# DDR.net
KiCad netlist of a schematic drawn in Altium Designer
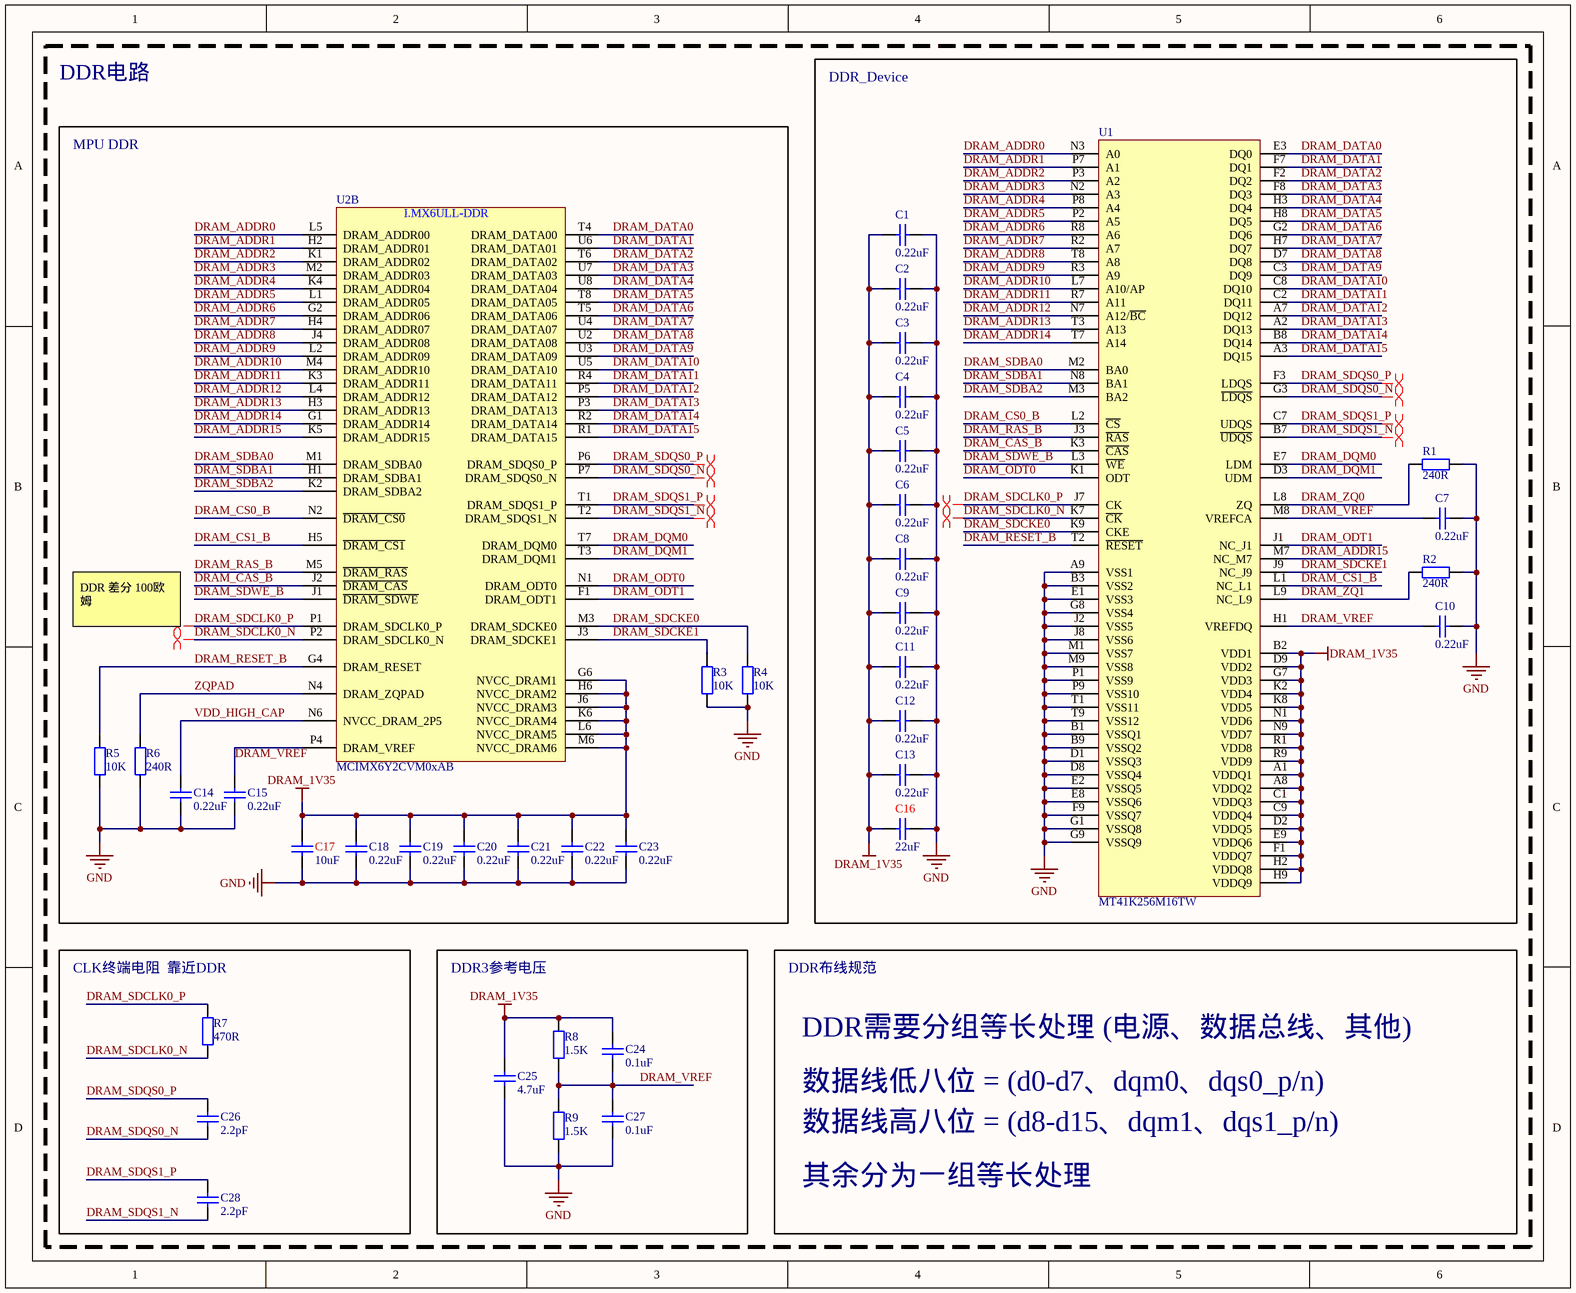
[diagram p0: DDR.SchDoc]

(export (version "E")
  (design (tool "Eeschema 10.0.6"))
  (components
    (comp (ref "C1")
      (value "0.22uF")
      (footprint "0402_C")
      (description "贴片电容")
      (libsource (lib "My_Devices") (part "0402_C"))
    )
    (comp (ref "C2")
      (value "0.22uF")
      (footprint "0402_C")
      (description "贴片电容")
      (libsource (lib "My_Devices") (part "0402_C"))
    )
    (comp (ref "C3")
      (value "0.22uF")
      (footprint "0402_C")
      (description "贴片电容")
      (libsource (lib "My_Devices") (part "0402_C"))
    )
    (comp (ref "C4")
      (value "0.22uF")
      (footprint "0402_C")
      (description "贴片电容")
      (libsource (lib "My_Devices") (part "0402_C"))
    )
    (comp (ref "C5")
      (value "0.22uF")
      (footprint "0402_C")
      (description "贴片电容")
      (libsource (lib "My_Devices") (part "0402_C"))
    )
    (comp (ref "C6")
      (value "0.22uF")
      (footprint "0402_C")
      (description "贴片电容")
      (libsource (lib "My_Devices") (part "0402_C"))
    )
    (comp (ref "C7")
      (value "0.22uF")
      (footprint "0402_C")
      (description "贴片电容")
      (libsource (lib "My_Devices") (part "0402_C"))
    )
    (comp (ref "C8")
      (value "0.22uF")
      (footprint "0402_C")
      (description "贴片电容")
      (libsource (lib "My_Devices") (part "0402_C"))
    )
    (comp (ref "C9")
      (value "0.22uF")
      (footprint "0402_C")
      (description "贴片电容")
      (libsource (lib "My_Devices") (part "0402_C"))
    )
    (comp (ref "C10")
      (value "0.22uF")
      (footprint "0402_C")
      (description "贴片电容")
      (libsource (lib "My_Devices") (part "0402_C"))
    )
    (comp (ref "C11")
      (value "0.22uF")
      (footprint "0402_C")
      (description "贴片电容")
      (libsource (lib "My_Devices") (part "0402_C"))
    )
    (comp (ref "C12")
      (value "0.22uF")
      (footprint "0402_C")
      (description "贴片电容")
      (libsource (lib "My_Devices") (part "0402_C"))
    )
    (comp (ref "C13")
      (value "0.22uF")
      (footprint "0402_C")
      (description "贴片电容")
      (libsource (lib "My_Devices") (part "0402_C"))
    )
    (comp (ref "C14")
      (value "0.22uF")
      (footprint "0402_C")
      (description "贴片电容")
      (libsource (lib "My_Devices") (part "0402_C"))
    )
    (comp (ref "C15")
      (value "0.22uF")
      (footprint "0402_C")
      (description "贴片电容")
      (libsource (lib "My_Devices") (part "0402_C"))
    )
    (comp (ref "C16")
      (value "22uF")
      (footprint "0603_C _MINI")
      (description "贴片电容")
      (libsource (lib "My_Devices") (part "0603_C_MINI"))
    )
    (comp (ref "C17")
      (value "10uF")
      (footprint "0603_C _MINI")
      (description "贴片电容")
      (libsource (lib "My_Devices") (part "0603_C_MINI"))
    )
    (comp (ref "C18")
      (value "0.22uF")
      (footprint "0402_C")
      (description "贴片电容")
      (libsource (lib "My_Devices") (part "0402_C"))
    )
    (comp (ref "C19")
      (value "0.22uF")
      (footprint "0402_C")
      (description "贴片电容")
      (libsource (lib "My_Devices") (part "0402_C"))
    )
    (comp (ref "C20")
      (value "0.22uF")
      (footprint "0402_C")
      (description "贴片电容")
      (libsource (lib "My_Devices") (part "0402_C"))
    )
    (comp (ref "C21")
      (value "0.22uF")
      (footprint "0402_C")
      (description "贴片电容")
      (libsource (lib "My_Devices") (part "0402_C"))
    )
    (comp (ref "C22")
      (value "0.22uF")
      (footprint "0402_C")
      (description "贴片电容")
      (libsource (lib "My_Devices") (part "0402_C"))
    )
    (comp (ref "C23")
      (value "0.22uF")
      (footprint "0402_C")
      (description "贴片电容")
      (libsource (lib "My_Devices") (part "0402_C"))
    )
    (comp (ref "C24")
      (value "0.1uF")
      (footprint "0402_C")
      (description "贴片电容")
      (libsource (lib "My_Devices") (part "0402_C"))
    )
    (comp (ref "C25")
      (value "4.7uF")
      (footprint "0402_C")
      (description "贴片电容")
      (libsource (lib "My_Devices") (part "0402_C"))
    )
    (comp (ref "C26")
      (value "2.2pF")
      (footprint "0402_C")
      (description "贴片电容")
      (libsource (lib "My_Devices") (part "0402_C"))
    )
    (comp (ref "C27")
      (value "0.1uF")
      (footprint "0402_C")
      (description "贴片电容")
      (libsource (lib "My_Devices") (part "0402_C"))
    )
    (comp (ref "C28")
      (value "2.2pF")
      (footprint "0402_C")
      (description "贴片电容")
      (libsource (lib "My_Devices") (part "0402_C"))
    )
    (comp (ref "R1")
      (value "240R")
      (footprint "0402_R")
      (description "贴片电阻")
      (libsource (lib "My_Devices") (part "0402_R"))
    )
    (comp (ref "R2")
      (value "240R")
      (footprint "0402_R")
      (description "贴片电阻")
      (libsource (lib "My_Devices") (part "0402_R"))
    )
    (comp (ref "R3")
      (value "10K")
      (footprint "0402_R")
      (description "贴片电阻")
      (libsource (lib "") (part "0402_R_1"))
    )
    (comp (ref "R4")
      (value "10K")
      (footprint "0402_R")
      (description "贴片电阻")
      (libsource (lib "") (part "0402_R_1"))
    )
    (comp (ref "R5")
      (value "10K")
      (footprint "0402_R")
      (description "贴片电阻")
      (libsource (lib "") (part "0402_R_1"))
    )
    (comp (ref "R6")
      (value "240R")
      (footprint "0402_R")
      (description "贴片电阻")
      (libsource (lib "") (part "0402_R_1"))
    )
    (comp (ref "R7")
      (value "470R")
      (footprint "0402_R")
      (description "贴片电阻")
      (libsource (lib "") (part "0402_R_1"))
    )
    (comp (ref "R8")
      (value "1.5K")
      (footprint "0402_R")
      (description "贴片电阻")
      (libsource (lib "") (part "0402_R_1"))
    )
    (comp (ref "R9")
      (value "1.5K")
      (footprint "0402_R")
      (description "贴片电阻")
      (libsource (lib "") (part "0402_R_1"))
    )
    (comp (ref "U1")
      (value "MT41K256M16TW")
      (footprint "BGA96")
      (libsource (lib "Linux_Core") (part "MT41K256M16TW"))
    )
    (comp (ref "U2")
      (value "MCIMX6Y2CVM0xAB")
      (footprint "BGA289_17x17_0.8Pitch")
      (libsource (lib "Linux_Core") (part "MCIMX6Y2CVM0xAB"))
    )
  )
  (nets
    (net (code "1") (name "/DRAM_ADDR0") (class "Default")
      (node (ref "U1") (pin "N3") (pinfunction "A0_N3") (pintype "passive"))
      (node (ref "U2") (pin "L5") (pinfunction "DRAM_ADDR00_L5") (pintype "passive"))
    )
    (net (code "2") (name "/DRAM_ADDR1") (class "Default")
      (node (ref "U1") (pin "P7") (pinfunction "A1_P7") (pintype "passive"))
      (node (ref "U2") (pin "H2") (pinfunction "DRAM_ADDR01_H2") (pintype "passive"))
    )
    (net (code "3") (name "/DRAM_ADDR2") (class "Default")
      (node (ref "U1") (pin "P3") (pinfunction "A2_P3") (pintype "passive"))
      (node (ref "U2") (pin "K1") (pinfunction "DRAM_ADDR02_K1") (pintype "passive"))
    )
    (net (code "4") (name "/DRAM_ADDR3") (class "Default")
      (node (ref "U1") (pin "N2") (pinfunction "A3_N2") (pintype "passive"))
      (node (ref "U2") (pin "M2") (pinfunction "DRAM_ADDR03_M2") (pintype "passive"))
    )
    (net (code "5") (name "/DRAM_ADDR4") (class "Default")
      (node (ref "U1") (pin "P8") (pinfunction "A4_P8") (pintype "passive"))
      (node (ref "U2") (pin "K4") (pinfunction "DRAM_ADDR04_K4") (pintype "passive"))
    )
    (net (code "6") (name "/DRAM_ADDR5") (class "Default")
      (node (ref "U1") (pin "P2") (pinfunction "A5_P2") (pintype "passive"))
      (node (ref "U2") (pin "L1") (pinfunction "DRAM_ADDR05_L1") (pintype "passive"))
    )
    (net (code "7") (name "/DRAM_ADDR6") (class "Default")
      (node (ref "U1") (pin "R8") (pinfunction "A6_R8") (pintype "passive"))
      (node (ref "U2") (pin "G2") (pinfunction "DRAM_ADDR06_G2") (pintype "passive"))
    )
    (net (code "8") (name "/DRAM_ADDR7") (class "Default")
      (node (ref "U1") (pin "R2") (pinfunction "A7_R2") (pintype "passive"))
      (node (ref "U2") (pin "H4") (pinfunction "DRAM_ADDR07_H4") (pintype "passive"))
    )
    (net (code "9") (name "/DRAM_ADDR8") (class "Default")
      (node (ref "U1") (pin "T8") (pinfunction "A8_T8") (pintype "passive"))
      (node (ref "U2") (pin "J4") (pinfunction "DRAM_ADDR08_J4") (pintype "passive"))
    )
    (net (code "10") (name "/DRAM_ADDR9") (class "Default")
      (node (ref "U1") (pin "R3") (pinfunction "A9_R3") (pintype "passive"))
      (node (ref "U2") (pin "L2") (pinfunction "DRAM_ADDR09_L2") (pintype "passive"))
    )
    (net (code "11") (name "/DRAM_ADDR10") (class "Default")
      (node (ref "U1") (pin "L7") (pinfunction "A10/AP_L7") (pintype "passive"))
      (node (ref "U2") (pin "M4") (pinfunction "DRAM_ADDR10_M4") (pintype "passive"))
    )
    (net (code "12") (name "/DRAM_ADDR11") (class "Default")
      (node (ref "U1") (pin "R7") (pinfunction "A11_R7") (pintype "passive"))
      (node (ref "U2") (pin "K3") (pinfunction "DRAM_ADDR11_K3") (pintype "passive"))
    )
    (net (code "13") (name "/DRAM_ADDR12") (class "Default")
      (node (ref "U1") (pin "N7") (pinfunction "A12/~{BC}_N7") (pintype "passive"))
      (node (ref "U2") (pin "L4") (pinfunction "DRAM_ADDR12_L4") (pintype "passive"))
    )
    (net (code "14") (name "/DRAM_ADDR13") (class "Default")
      (node (ref "U1") (pin "T3") (pinfunction "A13_T3") (pintype "passive"))
      (node (ref "U2") (pin "H3") (pinfunction "DRAM_ADDR13_H3") (pintype "passive"))
    )
    (net (code "15") (name "/DRAM_ADDR14") (class "Default")
      (node (ref "U1") (pin "T7") (pinfunction "A14_T7") (pintype "passive"))
      (node (ref "U2") (pin "G1") (pinfunction "DRAM_ADDR14_G1") (pintype "passive"))
    )
    (net (code "16") (name "/DRAM_ADDR15") (class "Default")
      (node (ref "U1") (pin "M7") (pinfunction "NC_M7_M7") (pintype "passive"))
      (node (ref "U2") (pin "K5") (pinfunction "DRAM_ADDR15_K5") (pintype "passive"))
    )
    (net (code "17") (name "/DRAM_CAS_B") (class "Default")
      (node (ref "U1") (pin "K3") (pinfunction "~{CAS}_K3") (pintype "passive"))
      (node (ref "U2") (pin "J2") (pinfunction "~{DRAM_CAS}_J2") (pintype "passive"))
    )
    (net (code "18") (name "/DRAM_CS0_B") (class "Default")
      (node (ref "U1") (pin "L2") (pinfunction "~{CS}_L2") (pintype "passive"))
      (node (ref "U2") (pin "N2") (pinfunction "~{DRAM_CS0}_N2") (pintype "passive"))
    )
    (net (code "19") (name "/DRAM_CS1_B") (class "Default")
      (node (ref "U1") (pin "L1") (pinfunction "NC_L1_L1") (pintype "passive"))
      (node (ref "U2") (pin "H5") (pinfunction "~{DRAM_CS1}_H5") (pintype "passive"))
    )
    (net (code "20") (name "/DRAM_DATA0") (class "Default")
      (node (ref "U1") (pin "E3") (pinfunction "DQ0_E3") (pintype "passive"))
      (node (ref "U2") (pin "T4") (pinfunction "DRAM_DATA00_T4") (pintype "passive"))
    )
    (net (code "21") (name "/DRAM_DATA1") (class "Default")
      (node (ref "U1") (pin "F7") (pinfunction "DQ1_F7") (pintype "passive"))
      (node (ref "U2") (pin "U6") (pinfunction "DRAM_DATA01_U6") (pintype "passive"))
    )
    (net (code "22") (name "/DRAM_DATA2") (class "Default")
      (node (ref "U1") (pin "F2") (pinfunction "DQ2_F2") (pintype "passive"))
      (node (ref "U2") (pin "T6") (pinfunction "DRAM_DATA02_T6") (pintype "passive"))
    )
    (net (code "23") (name "/DRAM_DATA3") (class "Default")
      (node (ref "U1") (pin "F8") (pinfunction "DQ3_F8") (pintype "passive"))
      (node (ref "U2") (pin "U7") (pinfunction "DRAM_DATA03_U7") (pintype "passive"))
    )
    (net (code "24") (name "/DRAM_DATA4") (class "Default")
      (node (ref "U1") (pin "H3") (pinfunction "DQ4_H3") (pintype "passive"))
      (node (ref "U2") (pin "U8") (pinfunction "DRAM_DATA04_U8") (pintype "passive"))
    )
    (net (code "25") (name "/DRAM_DATA5") (class "Default")
      (node (ref "U1") (pin "H8") (pinfunction "DQ5_H8") (pintype "passive"))
      (node (ref "U2") (pin "T8") (pinfunction "DRAM_DATA05_T8") (pintype "passive"))
    )
    (net (code "26") (name "/DRAM_DATA6") (class "Default")
      (node (ref "U1") (pin "G2") (pinfunction "DQ6_G2") (pintype "passive"))
      (node (ref "U2") (pin "T5") (pinfunction "DRAM_DATA06_T5") (pintype "passive"))
    )
    (net (code "27") (name "/DRAM_DATA7") (class "Default")
      (node (ref "U1") (pin "H7") (pinfunction "DQ7_H7") (pintype "passive"))
      (node (ref "U2") (pin "U4") (pinfunction "DRAM_DATA07_U4") (pintype "passive"))
    )
    (net (code "28") (name "/DRAM_DATA8") (class "Default")
      (node (ref "U1") (pin "D7") (pinfunction "DQ8_D7") (pintype "passive"))
      (node (ref "U2") (pin "U2") (pinfunction "DRAM_DATA08_U2") (pintype "passive"))
    )
    (net (code "29") (name "/DRAM_DATA9") (class "Default")
      (node (ref "U1") (pin "C3") (pinfunction "DQ9_C3") (pintype "passive"))
      (node (ref "U2") (pin "U3") (pinfunction "DRAM_DATA09_U3") (pintype "passive"))
    )
    (net (code "30") (name "/DRAM_DATA10") (class "Default")
      (node (ref "U1") (pin "C8") (pinfunction "DQ10_C8") (pintype "passive"))
      (node (ref "U2") (pin "U5") (pinfunction "DRAM_DATA10_U5") (pintype "passive"))
    )
    (net (code "31") (name "/DRAM_DATA11") (class "Default")
      (node (ref "U1") (pin "C2") (pinfunction "DQ11_C2") (pintype "passive"))
      (node (ref "U2") (pin "R4") (pinfunction "DRAM_DATA11_R4") (pintype "passive"))
    )
    (net (code "32") (name "/DRAM_DATA12") (class "Default")
      (node (ref "U1") (pin "A7") (pinfunction "DQ12_A7") (pintype "passive"))
      (node (ref "U2") (pin "P5") (pinfunction "DRAM_DATA12_P5") (pintype "passive"))
    )
    (net (code "33") (name "/DRAM_DATA13") (class "Default")
      (node (ref "U1") (pin "A2") (pinfunction "DQ13_A2") (pintype "passive"))
      (node (ref "U2") (pin "P3") (pinfunction "DRAM_DATA13_P3") (pintype "passive"))
    )
    (net (code "34") (name "/DRAM_DATA14") (class "Default")
      (node (ref "U1") (pin "B8") (pinfunction "DQ14_B8") (pintype "passive"))
      (node (ref "U2") (pin "R2") (pinfunction "DRAM_DATA14_R2") (pintype "passive"))
    )
    (net (code "35") (name "/DRAM_DATA15") (class "Default")
      (node (ref "U1") (pin "A3") (pinfunction "DQ15_A3") (pintype "passive"))
      (node (ref "U2") (pin "R1") (pinfunction "DRAM_DATA15_R1") (pintype "passive"))
    )
    (net (code "36") (name "/DRAM_DQM0") (class "Default")
      (node (ref "U1") (pin "E7") (pinfunction "LDM_E7") (pintype "passive"))
      (node (ref "U2") (pin "T7") (pinfunction "DRAM_DQM0_T7") (pintype "passive"))
    )
    (net (code "37") (name "/DRAM_DQM1") (class "Default")
      (node (ref "U1") (pin "D3") (pinfunction "UDM_D3") (pintype "passive"))
      (node (ref "U2") (pin "T3") (pinfunction "DRAM_DQM1_T3") (pintype "passive"))
    )
    (net (code "38") (name "/DRAM_ODT0") (class "Default")
      (node (ref "U1") (pin "K1") (pinfunction "ODT_K1") (pintype "passive"))
      (node (ref "U2") (pin "N1") (pinfunction "DRAM_ODT0_N1") (pintype "passive"))
    )
    (net (code "39") (name "/DRAM_ODT1") (class "Default")
      (node (ref "U1") (pin "J1") (pinfunction "NC_J1_J1") (pintype "passive"))
      (node (ref "U2") (pin "F1") (pinfunction "DRAM_ODT1_F1") (pintype "passive"))
    )
    (net (code "40") (name "/DRAM_RAS_B") (class "Default")
      (node (ref "U1") (pin "J3") (pinfunction "~{RAS}_J3") (pintype "passive"))
      (node (ref "U2") (pin "M5") (pinfunction "~{DRAM_RAS}_M5") (pintype "passive"))
    )
    (net (code "41") (name "/DRAM_RESET_B") (class "Default")
      (node (ref "R5") (pin "2") (pinfunction "2_2") (pintype "passive"))
      (node (ref "U1") (pin "T2") (pinfunction "~{RESET}_T2") (pintype "passive"))
      (node (ref "U2") (pin "G4") (pinfunction "DRAM_RESET_G4") (pintype "passive"))
    )
    (net (code "42") (name "/DRAM_SDBA0") (class "Default")
      (node (ref "U1") (pin "M2") (pinfunction "BA0_M2") (pintype "passive"))
      (node (ref "U2") (pin "M1") (pinfunction "DRAM_SDBA0_M1") (pintype "passive"))
    )
    (net (code "43") (name "/DRAM_SDBA1") (class "Default")
      (node (ref "U1") (pin "N8") (pinfunction "BA1_N8") (pintype "passive"))
      (node (ref "U2") (pin "H1") (pinfunction "DRAM_SDBA1_H1") (pintype "passive"))
    )
    (net (code "44") (name "/DRAM_SDBA2") (class "Default")
      (node (ref "U1") (pin "M3") (pinfunction "BA2_M3") (pintype "passive"))
      (node (ref "U2") (pin "K2") (pinfunction "DRAM_SDBA2_K2") (pintype "passive"))
    )
    (net (code "45") (name "/DRAM_SDCKE0") (class "Default")
      (node (ref "R4") (pin "2") (pinfunction "2_2") (pintype "passive"))
      (node (ref "U1") (pin "K9") (pinfunction "CKE_K9") (pintype "passive"))
      (node (ref "U2") (pin "M3") (pinfunction "DRAM_SDCKE0_M3") (pintype "passive"))
    )
    (net (code "46") (name "/DRAM_SDCKE1") (class "Default")
      (node (ref "R3") (pin "2") (pinfunction "2_2") (pintype "passive"))
      (node (ref "U1") (pin "J9") (pinfunction "NC_J9_J9") (pintype "passive"))
      (node (ref "U2") (pin "J3") (pinfunction "DRAM_SDCKE1_J3") (pintype "passive"))
    )
    (net (code "47") (name "/DRAM_SDCLK0_N") (class "Default")
      (node (ref "R7") (pin "1") (pinfunction "1_1") (pintype "passive"))
      (node (ref "U1") (pin "K7") (pinfunction "~{CK}_K7") (pintype "passive"))
      (node (ref "U2") (pin "P2") (pinfunction "DRAM_SDCLK0_N_P2") (pintype "passive"))
    )
    (net (code "48") (name "/DRAM_SDCLK0_P") (class "Default")
      (node (ref "R7") (pin "2") (pinfunction "2_2") (pintype "passive"))
      (node (ref "U1") (pin "J7") (pinfunction "CK_J7") (pintype "passive"))
      (node (ref "U2") (pin "P1") (pinfunction "DRAM_SDCLK0_P_P1") (pintype "passive"))
    )
    (net (code "49") (name "/DRAM_SDQS0_N") (class "Default")
      (node (ref "C26") (pin "1") (pinfunction "1_1") (pintype "passive"))
      (node (ref "U1") (pin "G3") (pinfunction "~{LDQS}_G3") (pintype "passive"))
      (node (ref "U2") (pin "P7") (pinfunction "DRAM_SDQS0_N_P7") (pintype "passive"))
    )
    (net (code "50") (name "/DRAM_SDQS0_P") (class "Default")
      (node (ref "C26") (pin "2") (pinfunction "2_2") (pintype "passive"))
      (node (ref "U1") (pin "F3") (pinfunction "LDQS_F3") (pintype "passive"))
      (node (ref "U2") (pin "P6") (pinfunction "DRAM_SDQS0_P_P6") (pintype "passive"))
    )
    (net (code "51") (name "/DRAM_SDQS1_N") (class "Default")
      (node (ref "C28") (pin "1") (pinfunction "1_1") (pintype "passive"))
      (node (ref "U1") (pin "B7") (pinfunction "~{UDQS}_B7") (pintype "passive"))
      (node (ref "U2") (pin "T2") (pinfunction "DRAM_SDQS1_N_T2") (pintype "passive"))
    )
    (net (code "52") (name "/DRAM_SDQS1_P") (class "Default")
      (node (ref "C28") (pin "2") (pinfunction "2_2") (pintype "passive"))
      (node (ref "U1") (pin "C7") (pinfunction "UDQS_C7") (pintype "passive"))
      (node (ref "U2") (pin "T1") (pinfunction "DRAM_SDQS1_P_T1") (pintype "passive"))
    )
    (net (code "53") (name "/DRAM_SDWE_B") (class "Default")
      (node (ref "U1") (pin "L3") (pinfunction "~{WE}_L3") (pintype "passive"))
      (node (ref "U2") (pin "J1") (pinfunction "~{DRAM_SDWE}_J1") (pintype "passive"))
    )
    (net (code "54") (name "/DRAM_VREF") (class "Default")
      (node (ref "C10") (pin "1") (pinfunction "1_1") (pintype "passive"))
      (node (ref "C15") (pin "2") (pinfunction "2_2") (pintype "passive"))
      (node (ref "C24") (pin "1") (pinfunction "1_1") (pintype "passive"))
      (node (ref "C27") (pin "2") (pinfunction "2_2") (pintype "passive"))
      (node (ref "C7") (pin "1") (pinfunction "1_1") (pintype "passive"))
      (node (ref "R8") (pin "1") (pinfunction "1_1") (pintype "passive"))
      (node (ref "R9") (pin "2") (pinfunction "2_2") (pintype "passive"))
      (node (ref "U1") (pin "H1") (pinfunction "VREFDQ_H1") (pintype "passive"))
      (node (ref "U1") (pin "M8") (pinfunction "VREFCA_M8") (pintype "passive"))
      (node (ref "U2") (pin "P4") (pinfunction "DRAM_VREF_P4") (pintype "passive"))
    )
    (net (code "55") (name "/DRAM_ZQ0") (class "Default")
      (node (ref "R1") (pin "2") (pinfunction "2_2") (pintype "passive"))
      (node (ref "U1") (pin "L8") (pinfunction "ZQ_L8") (pintype "passive"))
    )
    (net (code "56") (name "/DRAM_ZQ1") (class "Default")
      (node (ref "R2") (pin "2") (pinfunction "2_2") (pintype "passive"))
      (node (ref "U1") (pin "L9") (pinfunction "NC_L9_L9") (pintype "passive"))
    )
    (net (code "57") (name "/VDD_HIGH_CAP") (class "Default")
      (node (ref "C14") (pin "2") (pinfunction "2_2") (pintype "passive"))
      (node (ref "U2") (pin "N6") (pinfunction "NVCC_DRAM_2P5_N6") (pintype "passive"))
    )
    (net (code "58") (name "/ZQPAD") (class "Default")
      (node (ref "R6") (pin "2") (pinfunction "2_2") (pintype "passive"))
      (node (ref "U2") (pin "N4") (pinfunction "DRAM_ZQPAD_N4") (pintype "passive"))
    )
    (net (code "59") (name "DRAM_1V35") (class "Default")
      (node (ref "C1") (pin "2") (pinfunction "2_2") (pintype "passive"))
      (node (ref "C11") (pin "2") (pinfunction "2_2") (pintype "passive"))
      (node (ref "C12") (pin "2") (pinfunction "2_2") (pintype "passive"))
      (node (ref "C13") (pin "2") (pinfunction "2_2") (pintype "passive"))
      (node (ref "C16") (pin "1") (pinfunction "1_1") (pintype "passive"))
      (node (ref "C17") (pin "2") (pinfunction "2_2") (pintype "passive"))
      (node (ref "C18") (pin "2") (pinfunction "2_2") (pintype "passive"))
      (node (ref "C19") (pin "2") (pinfunction "2_2") (pintype "passive"))
      (node (ref "C2") (pin "2") (pinfunction "2_2") (pintype "passive"))
      (node (ref "C20") (pin "2") (pinfunction "2_2") (pintype "passive"))
      (node (ref "C21") (pin "2") (pinfunction "2_2") (pintype "passive"))
      (node (ref "C22") (pin "2") (pinfunction "2_2") (pintype "passive"))
      (node (ref "C23") (pin "2") (pinfunction "2_2") (pintype "passive"))
      (node (ref "C24") (pin "2") (pinfunction "2_2") (pintype "passive"))
      (node (ref "C25") (pin "2") (pinfunction "2_2") (pintype "passive"))
      (node (ref "C3") (pin "2") (pinfunction "2_2") (pintype "passive"))
      (node (ref "C4") (pin "2") (pinfunction "2_2") (pintype "passive"))
      (node (ref "C5") (pin "2") (pinfunction "2_2") (pintype "passive"))
      (node (ref "C6") (pin "2") (pinfunction "2_2") (pintype "passive"))
      (node (ref "C8") (pin "2") (pinfunction "2_2") (pintype "passive"))
      (node (ref "C9") (pin "2") (pinfunction "2_2") (pintype "passive"))
      (node (ref "R8") (pin "2") (pinfunction "2_2") (pintype "passive"))
      (node (ref "U1") (pin "A1") (pinfunction "VDDQ1_A1") (pintype "passive"))
      (node (ref "U1") (pin "A8") (pinfunction "VDDQ2_A8") (pintype "passive"))
      (node (ref "U1") (pin "B2") (pinfunction "VDD1_B2") (pintype "passive"))
      (node (ref "U1") (pin "C1") (pinfunction "VDDQ3_C1") (pintype "passive"))
      (node (ref "U1") (pin "C9") (pinfunction "VDDQ4_C9") (pintype "passive"))
      (node (ref "U1") (pin "D2") (pinfunction "VDDQ5_D2") (pintype "passive"))
      (node (ref "U1") (pin "D9") (pinfunction "VDD2_D9") (pintype "passive"))
      (node (ref "U1") (pin "E9") (pinfunction "VDDQ6_E9") (pintype "passive"))
      (node (ref "U1") (pin "F1") (pinfunction "VDDQ7_F1") (pintype "passive"))
      (node (ref "U1") (pin "G7") (pinfunction "VDD3_G7") (pintype "passive"))
      (node (ref "U1") (pin "H2") (pinfunction "VDDQ8_H2") (pintype "passive"))
      (node (ref "U1") (pin "H9") (pinfunction "VDDQ9_H9") (pintype "passive"))
      (node (ref "U1") (pin "K2") (pinfunction "VDD4_K2") (pintype "passive"))
      (node (ref "U1") (pin "K8") (pinfunction "VDD5_K8") (pintype "passive"))
      (node (ref "U1") (pin "N1") (pinfunction "VDD6_N1") (pintype "passive"))
      (node (ref "U1") (pin "N9") (pinfunction "VDD7_N9") (pintype "passive"))
      (node (ref "U1") (pin "R1") (pinfunction "VDD8_R1") (pintype "passive"))
      (node (ref "U1") (pin "R9") (pinfunction "VDD9_R9") (pintype "passive"))
      (node (ref "U2") (pin "G6") (pinfunction "NVCC_DRAM1_G6") (pintype "passive"))
      (node (ref "U2") (pin "H6") (pinfunction "NVCC_DRAM2_H6") (pintype "passive"))
      (node (ref "U2") (pin "J6") (pinfunction "NVCC_DRAM3_J6") (pintype "passive"))
      (node (ref "U2") (pin "K6") (pinfunction "NVCC_DRAM4_K6") (pintype "passive"))
      (node (ref "U2") (pin "L6") (pinfunction "NVCC_DRAM5_L6") (pintype "passive"))
      (node (ref "U2") (pin "M6") (pinfunction "NVCC_DRAM6_M6") (pintype "passive"))
    )
    (net (code "60") (name "GND") (class "Default")
      (node (ref "C1") (pin "1") (pinfunction "1_1") (pintype "passive"))
      (node (ref "C10") (pin "2") (pinfunction "2_2") (pintype "passive"))
      (node (ref "C11") (pin "1") (pinfunction "1_1") (pintype "passive"))
      (node (ref "C12") (pin "1") (pinfunction "1_1") (pintype "passive"))
      (node (ref "C13") (pin "1") (pinfunction "1_1") (pintype "passive"))
      (node (ref "C14") (pin "1") (pinfunction "1_1") (pintype "passive"))
      (node (ref "C15") (pin "1") (pinfunction "1_1") (pintype "passive"))
      (node (ref "C16") (pin "2") (pinfunction "2_2") (pintype "passive"))
      (node (ref "C17") (pin "1") (pinfunction "1_1") (pintype "passive"))
      (node (ref "C18") (pin "1") (pinfunction "1_1") (pintype "passive"))
      (node (ref "C19") (pin "1") (pinfunction "1_1") (pintype "passive"))
      (node (ref "C2") (pin "1") (pinfunction "1_1") (pintype "passive"))
      (node (ref "C20") (pin "1") (pinfunction "1_1") (pintype "passive"))
      (node (ref "C21") (pin "1") (pinfunction "1_1") (pintype "passive"))
      (node (ref "C22") (pin "1") (pinfunction "1_1") (pintype "passive"))
      (node (ref "C23") (pin "1") (pinfunction "1_1") (pintype "passive"))
      (node (ref "C25") (pin "1") (pinfunction "1_1") (pintype "passive"))
      (node (ref "C27") (pin "1") (pinfunction "1_1") (pintype "passive"))
      (node (ref "C3") (pin "1") (pinfunction "1_1") (pintype "passive"))
      (node (ref "C4") (pin "1") (pinfunction "1_1") (pintype "passive"))
      (node (ref "C5") (pin "1") (pinfunction "1_1") (pintype "passive"))
      (node (ref "C6") (pin "1") (pinfunction "1_1") (pintype "passive"))
      (node (ref "C7") (pin "2") (pinfunction "2_2") (pintype "passive"))
      (node (ref "C8") (pin "1") (pinfunction "1_1") (pintype "passive"))
      (node (ref "C9") (pin "1") (pinfunction "1_1") (pintype "passive"))
      (node (ref "R1") (pin "1") (pinfunction "1_1") (pintype "passive"))
      (node (ref "R2") (pin "1") (pinfunction "1_1") (pintype "passive"))
      (node (ref "R3") (pin "1") (pinfunction "1_1") (pintype "passive"))
      (node (ref "R4") (pin "1") (pinfunction "1_1") (pintype "passive"))
      (node (ref "R5") (pin "1") (pinfunction "1_1") (pintype "passive"))
      (node (ref "R6") (pin "1") (pinfunction "1_1") (pintype "passive"))
      (node (ref "R9") (pin "1") (pinfunction "1_1") (pintype "passive"))
      (node (ref "U1") (pin "A9") (pinfunction "VSS1_A9") (pintype "passive"))
      (node (ref "U1") (pin "B1") (pinfunction "VSSQ1_B1") (pintype "passive"))
      (node (ref "U1") (pin "B3") (pinfunction "VSS2_B3") (pintype "passive"))
      (node (ref "U1") (pin "B9") (pinfunction "VSSQ2_B9") (pintype "passive"))
      (node (ref "U1") (pin "D1") (pinfunction "VSSQ3_D1") (pintype "passive"))
      (node (ref "U1") (pin "D8") (pinfunction "VSSQ4_D8") (pintype "passive"))
      (node (ref "U1") (pin "E1") (pinfunction "VSS3_E1") (pintype "passive"))
      (node (ref "U1") (pin "E2") (pinfunction "VSSQ5_E2") (pintype "passive"))
      (node (ref "U1") (pin "E8") (pinfunction "VSSQ6_E8") (pintype "passive"))
      (node (ref "U1") (pin "F9") (pinfunction "VSSQ7_F9") (pintype "passive"))
      (node (ref "U1") (pin "G1") (pinfunction "VSSQ8_G1") (pintype "passive"))
      (node (ref "U1") (pin "G8") (pinfunction "VSS4_G8") (pintype "passive"))
      (node (ref "U1") (pin "G9") (pinfunction "VSSQ9_G9") (pintype "passive"))
      (node (ref "U1") (pin "J2") (pinfunction "VSS5_J2") (pintype "passive"))
      (node (ref "U1") (pin "J8") (pinfunction "VSS6_J8") (pintype "passive"))
      (node (ref "U1") (pin "M1") (pinfunction "VSS7_M1") (pintype "passive"))
      (node (ref "U1") (pin "M9") (pinfunction "VSS8_M9") (pintype "passive"))
      (node (ref "U1") (pin "P1") (pinfunction "VSS9_P1") (pintype "passive"))
      (node (ref "U1") (pin "P9") (pinfunction "VSS10_P9") (pintype "passive"))
      (node (ref "U1") (pin "T1") (pinfunction "VSS11_T1") (pintype "passive"))
      (node (ref "U1") (pin "T9") (pinfunction "VSS12_T9") (pintype "passive"))
    )
  )
)
